# scrump.net
KiCad netlist of a schematic drawn in EAGLE
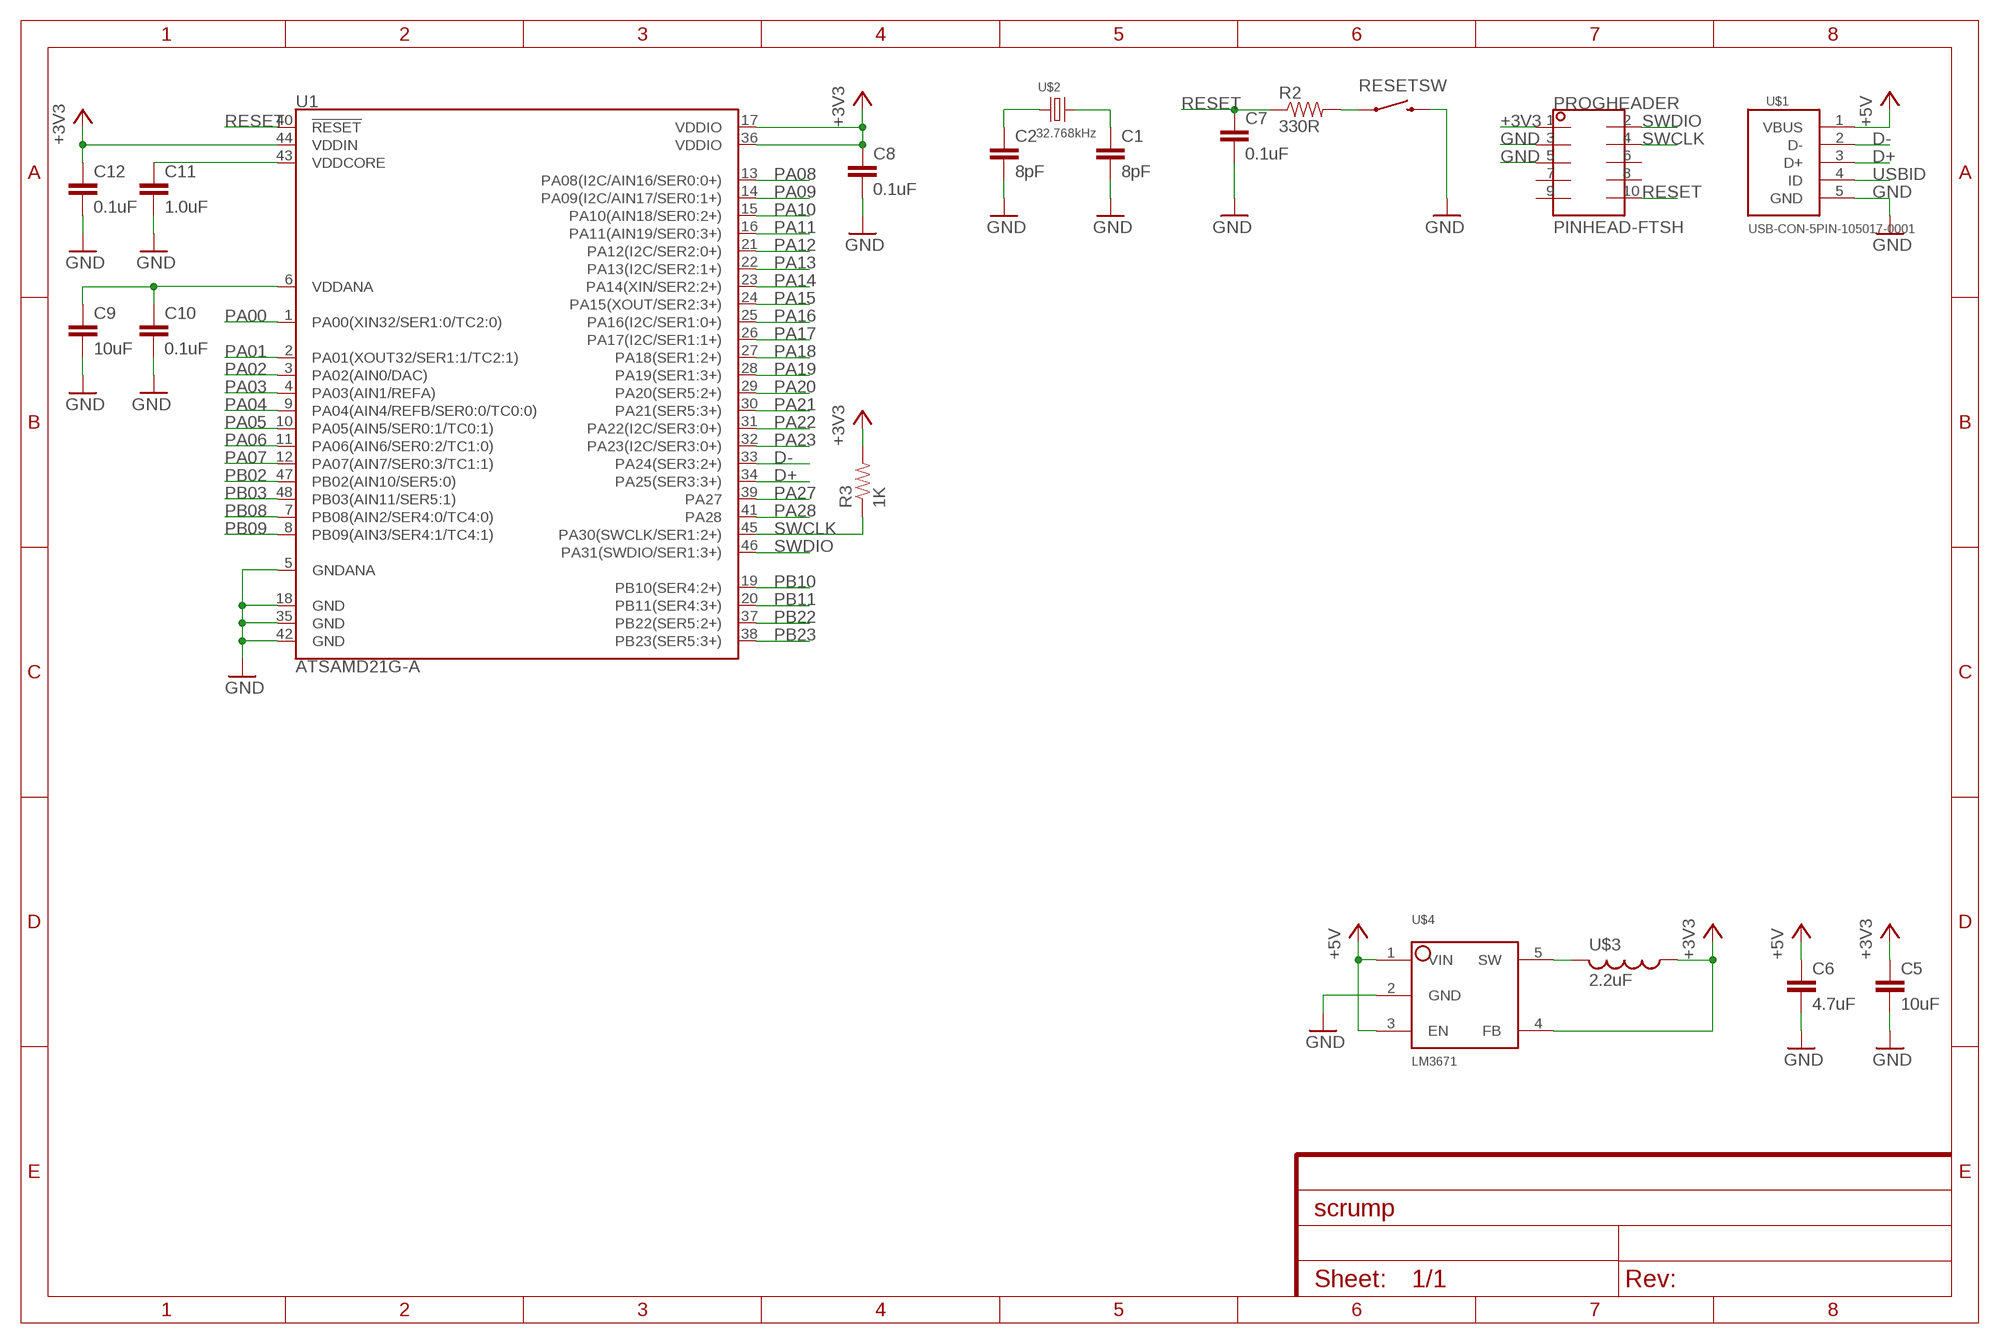
[diagram p0: schematic, sheet 1]

(export (version "E")
  (design (tool "Eeschema 10.0.6"))
  (components
    (comp (ref "C1")
      (value "8pF")
      (footprint "eagle-import:0603-CAP")
      (libsource (lib "eagle-import") (part "CAP0603-CAP"))
    )
    (comp (ref "C2")
      (value "8pF")
      (footprint "eagle-import:0603-CAP")
      (libsource (lib "eagle-import") (part "CAP0603-CAP"))
    )
    (comp (ref "C5")
      (value "10uF")
      (footprint "eagle-import:0603-CAP")
      (libsource (lib "eagle-import") (part "CAP0603-CAP"))
    )
    (comp (ref "C6")
      (value "4.7uF")
      (footprint "eagle-import:0603-CAP")
      (libsource (lib "eagle-import") (part "CAP0603-CAP"))
    )
    (comp (ref "C7")
      (value "0.1uF")
      (footprint "eagle-import:0603-CAP")
      (libsource (lib "eagle-import") (part "0.1UF-25V(+80/-20%)(0603)"))
    )
    (comp (ref "C8")
      (value "0.1uF")
      (footprint "eagle-import:0603-CAP")
      (libsource (lib "eagle-import") (part "CAP0603-CAP"))
    )
    (comp (ref "C9")
      (value "10uF")
      (footprint "eagle-import:0603-CAP")
      (libsource (lib "eagle-import") (part "CAP0603-CAP"))
    )
    (comp (ref "C10")
      (value "0.1uF")
      (footprint "eagle-import:0603-CAP")
      (libsource (lib "eagle-import") (part "CAP0603-CAP"))
    )
    (comp (ref "C11")
      (value "1.0uF")
      (footprint "eagle-import:0603-CAP")
      (libsource (lib "eagle-import") (part "CAP0603-CAP"))
    )
    (comp (ref "C12")
      (value "0.1uF")
      (footprint "eagle-import:0603-CAP")
      (libsource (lib "eagle-import") (part "CAP0603-CAP"))
    )
    (comp (ref "PROGHEADER")
      (value "PINHEAD-FTSH")
      (footprint "eagle-import:FTSH-105-01-XXX-DV-K")
      (libsource (lib "eagle-import") (part "PINHEAD-FTSH"))
    )
    (comp (ref "R2")
      (value "330R")
      (footprint "eagle-import:0603-RES")
      (libsource (lib "eagle-import") (part "RESISTOR0603"))
    )
    (comp (ref "R3")
      (value "1K")
      (footprint "eagle-import:0603-RES")
      (libsource (lib "eagle-import") (part "RESISTOR0603"))
    )
    (comp (ref "RESETSW")
      (value "PUSHBUTTON-SMD")
      (footprint "eagle-import:TACTILE-SMD-SWITCH")
      (libsource (lib "eagle-import") (part "PUSHBUTTON-SMD"))
    )
    (comp (ref "U$1")
      (value "USB-CON-5PIN-105017-0001")
      (footprint "eagle-import:USB-MICRO-MOLEX-105017-0001")
      (libsource (lib "eagle-import") (part "USB-CON-5PIN-105017-0001"))
    )
    (comp (ref "U$2")
      (value "32.768kHz")
      (footprint "eagle-import:ABS25")
      (libsource (lib "eagle-import") (part "CRYSTAL"))
    )
    (comp (ref "U$3")
      (value "2.2uF")
      (footprint "eagle-import:0806-INDUCTOR")
      (libsource (lib "eagle-import") (part "INDUCTOR"))
    )
    (comp (ref "U$4")
      (value "LM3671")
      (footprint "eagle-import:SOT23-5")
      (libsource (lib "eagle-import") (part "LM3671"))
    )
    (comp (ref "U1")
      (value "ATSAMD21G-A")
      (footprint "eagle-import:TQFP-48")
      (libsource (lib "eagle-import") (part "ATSAMD21G-A"))
    )
  )
  (nets
    (net (code "1") (name "+3V3") (class "Default")
      (node (ref "C12") (pin "1") (pinfunction "1_1") (pintype "passive"))
      (node (ref "C5") (pin "1") (pinfunction "1_1") (pintype "passive"))
      (node (ref "C8") (pin "1") (pinfunction "1_1") (pintype "passive"))
      (node (ref "PROGHEADER") (pin "1") (pinfunction "P$1_1") (pintype "bidirectional"))
      (node (ref "R3") (pin "2") (pinfunction "2_2") (pintype "passive"))
      (node (ref "U$3") (pin "1") (pinfunction "1_1") (pintype "passive"))
      (node (ref "U$4") (pin "4") (pinfunction "FB_4") (pintype "bidirectional"))
      (node (ref "U1") (pin "17") (pinfunction "VDDIO_17") (pintype "bidirectional"))
      (node (ref "U1") (pin "36") (pinfunction "VDDIO_36") (pintype "bidirectional"))
      (node (ref "U1") (pin "44") (pinfunction "VDDIN_44") (pintype "bidirectional"))
    )
    (net (code "2") (name "+5V") (class "Default")
      (node (ref "C6") (pin "1") (pinfunction "1_1") (pintype "passive"))
      (node (ref "U$1") (pin "1") (pinfunction "VBUS_1") (pintype "power_in"))
      (node (ref "U$4") (pin "1") (pinfunction "VIN_1") (pintype "bidirectional"))
      (node (ref "U$4") (pin "3") (pinfunction "EN_3") (pintype "bidirectional"))
    )
    (net (code "3") (name "/D+") (class "Default")
      (node (ref "U$1") (pin "3") (pinfunction "D+_3") (pintype "bidirectional"))
      (node (ref "U1") (pin "34") (pinfunction "PA25(SER3:3+)_34") (pintype "bidirectional"))
    )
    (net (code "4") (name "/D-") (class "Default")
      (node (ref "U$1") (pin "2") (pinfunction "D-_2") (pintype "bidirectional"))
      (node (ref "U1") (pin "33") (pinfunction "PA24(SER3:2+)_33") (pintype "bidirectional"))
    )
    (net (code "5") (name "/PA00") (class "Default")
      (node (ref "C2") (pin "1") (pinfunction "1_1") (pintype "passive"))
      (node (ref "U$2") (pin "P$1") (pinfunction "1_P$1") (pintype "passive"))
      (node (ref "U1") (pin "1") (pinfunction "PA00(XIN32/SER1:0/TC2:0)_1") (pintype "bidirectional"))
    )
    (net (code "6") (name "/PA01") (class "Default")
      (node (ref "C1") (pin "1") (pinfunction "1_1") (pintype "passive"))
      (node (ref "U$2") (pin "P$4") (pinfunction "3_P$4") (pintype "passive"))
      (node (ref "U1") (pin "2") (pinfunction "PA01(XOUT32/SER1:1/TC2:1)_2") (pintype "bidirectional"))
    )
    (net (code "7") (name "/PA02") (class "Default")
      (node (ref "U1") (pin "3") (pinfunction "PA02(AIN0/DAC)_3") (pintype "bidirectional"))
    )
    (net (code "8") (name "/PA03") (class "Default")
      (node (ref "U1") (pin "4") (pinfunction "PA03(AIN1/REFA)_4") (pintype "bidirectional"))
    )
    (net (code "9") (name "/PA04") (class "Default")
      (node (ref "U1") (pin "9") (pinfunction "PA04(AIN4/REFB/SER0:0/TC0:0)_9") (pintype "bidirectional"))
    )
    (net (code "10") (name "/PA05") (class "Default")
      (node (ref "U1") (pin "10") (pinfunction "PA05(AIN5/SER0:1/TC0:1)_10") (pintype "bidirectional"))
    )
    (net (code "11") (name "/PA06") (class "Default")
      (node (ref "U1") (pin "11") (pinfunction "PA06(AIN6/SER0:2/TC1:0)_11") (pintype "bidirectional"))
    )
    (net (code "12") (name "/PA07") (class "Default")
      (node (ref "U1") (pin "12") (pinfunction "PA07(AIN7/SER0:3/TC1:1)_12") (pintype "bidirectional"))
    )
    (net (code "13") (name "/PA08") (class "Default")
      (node (ref "U1") (pin "13") (pinfunction "PA08(I2C/AIN16/SER0:0+)_13") (pintype "bidirectional"))
    )
    (net (code "14") (name "/PA09") (class "Default")
      (node (ref "U1") (pin "14") (pinfunction "PA09(I2C/AIN17/SER0:1+)_14") (pintype "bidirectional"))
    )
    (net (code "15") (name "/PA10") (class "Default")
      (node (ref "U1") (pin "15") (pinfunction "PA10(AIN18/SER0:2+)_15") (pintype "bidirectional"))
    )
    (net (code "16") (name "/PA11") (class "Default")
      (node (ref "U1") (pin "16") (pinfunction "PA11(AIN19/SER0:3+)_16") (pintype "bidirectional"))
    )
    (net (code "17") (name "/PA12") (class "Default")
      (node (ref "U1") (pin "21") (pinfunction "PA12(I2C/SER2:0+)_21") (pintype "bidirectional"))
    )
    (net (code "18") (name "/PA13") (class "Default")
      (node (ref "U1") (pin "22") (pinfunction "PA13(I2C/SER2:1+)_22") (pintype "bidirectional"))
    )
    (net (code "19") (name "/PA14") (class "Default")
      (node (ref "U1") (pin "23") (pinfunction "PA14(XIN/SER2:2+)_23") (pintype "bidirectional"))
    )
    (net (code "20") (name "/PA15") (class "Default")
      (node (ref "U1") (pin "24") (pinfunction "PA15(XOUT/SER2:3+)_24") (pintype "bidirectional"))
    )
    (net (code "21") (name "/PA16") (class "Default")
      (node (ref "U1") (pin "25") (pinfunction "PA16(I2C/SER1:0+)_25") (pintype "bidirectional"))
    )
    (net (code "22") (name "/PA17") (class "Default")
      (node (ref "U1") (pin "26") (pinfunction "PA17(I2C/SER1:1+)_26") (pintype "bidirectional"))
    )
    (net (code "23") (name "/PA18") (class "Default")
      (node (ref "U1") (pin "27") (pinfunction "PA18(SER1:2+)_27") (pintype "bidirectional"))
    )
    (net (code "24") (name "/PA19") (class "Default")
      (node (ref "U1") (pin "28") (pinfunction "PA19(SER1:3+)_28") (pintype "bidirectional"))
    )
    (net (code "25") (name "/PA20") (class "Default")
      (node (ref "U1") (pin "29") (pinfunction "PA20(SER5:2+)_29") (pintype "bidirectional"))
    )
    (net (code "26") (name "/PA21") (class "Default")
      (node (ref "U1") (pin "30") (pinfunction "PA21(SER5:3+)_30") (pintype "bidirectional"))
    )
    (net (code "27") (name "/PA22") (class "Default")
      (node (ref "U1") (pin "31") (pinfunction "PA22(I2C/SER3:0+)_31") (pintype "bidirectional"))
    )
    (net (code "28") (name "/PA23") (class "Default")
      (node (ref "U1") (pin "32") (pinfunction "PA23(I2C/SER3:0+)_32") (pintype "bidirectional"))
    )
    (net (code "29") (name "/PA27") (class "Default")
      (node (ref "U1") (pin "39") (pinfunction "PA27_39") (pintype "bidirectional"))
    )
    (net (code "30") (name "/PA28") (class "Default")
      (node (ref "U1") (pin "41") (pinfunction "PA28_41") (pintype "bidirectional"))
    )
    (net (code "31") (name "/PB02") (class "Default")
      (node (ref "U1") (pin "47") (pinfunction "PB02(AIN10/SER5:0)_47") (pintype "bidirectional"))
    )
    (net (code "32") (name "/PB03") (class "Default")
      (node (ref "U1") (pin "48") (pinfunction "PB03(AIN11/SER5:1)_48") (pintype "bidirectional"))
    )
    (net (code "33") (name "/PB08") (class "Default")
      (node (ref "U1") (pin "7") (pinfunction "PB08(AIN2/SER4:0/TC4:0)_7") (pintype "bidirectional"))
    )
    (net (code "34") (name "/PB09") (class "Default")
      (node (ref "U1") (pin "8") (pinfunction "PB09(AIN3/SER4:1/TC4:1)_8") (pintype "bidirectional"))
    )
    (net (code "35") (name "/PB10") (class "Default")
      (node (ref "U1") (pin "19") (pinfunction "PB10(SER4:2+)_19") (pintype "bidirectional"))
    )
    (net (code "36") (name "/PB11") (class "Default")
      (node (ref "U1") (pin "20") (pinfunction "PB11(SER4:3+)_20") (pintype "bidirectional"))
    )
    (net (code "37") (name "/PB22") (class "Default")
      (node (ref "U1") (pin "37") (pinfunction "PB22(SER5:2+)_37") (pintype "bidirectional"))
    )
    (net (code "38") (name "/PB23") (class "Default")
      (node (ref "U1") (pin "38") (pinfunction "PB23(SER5:3+)_38") (pintype "bidirectional"))
    )
    (net (code "39") (name "/RESET") (class "Default")
      (node (ref "C7") (pin "1") (pinfunction "1_1") (pintype "passive"))
      (node (ref "PROGHEADER") (pin "10") (pinfunction "P$10_10") (pintype "bidirectional"))
      (node (ref "R2") (pin "1") (pinfunction "1_1") (pintype "passive"))
      (node (ref "U1") (pin "40") (pinfunction "~{RESET}_40") (pintype "bidirectional"))
    )
    (net (code "40") (name "/SWCLK") (class "Default")
      (node (ref "PROGHEADER") (pin "4") (pinfunction "P$4_4") (pintype "bidirectional"))
      (node (ref "R3") (pin "1") (pinfunction "1_1") (pintype "passive"))
      (node (ref "U1") (pin "45") (pinfunction "PA30(SWCLK/SER1:2+)_45") (pintype "bidirectional"))
    )
    (net (code "41") (name "/SWDIO") (class "Default")
      (node (ref "PROGHEADER") (pin "2") (pinfunction "P$2_2") (pintype "bidirectional"))
      (node (ref "U1") (pin "46") (pinfunction "PA31(SWDIO/SER1:3+)_46") (pintype "bidirectional"))
    )
    (net (code "42") (name "/USBID") (class "Default")
      (node (ref "U$1") (pin "4") (pinfunction "ID_4") (pintype "bidirectional"))
    )
    (net (code "43") (name "GND") (class "Default")
      (node (ref "C1") (pin "2") (pinfunction "2_2") (pintype "passive"))
      (node (ref "C10") (pin "2") (pinfunction "2_2") (pintype "passive"))
      (node (ref "C11") (pin "2") (pinfunction "2_2") (pintype "passive"))
      (node (ref "C12") (pin "2") (pinfunction "2_2") (pintype "passive"))
      (node (ref "C2") (pin "2") (pinfunction "2_2") (pintype "passive"))
      (node (ref "C5") (pin "2") (pinfunction "2_2") (pintype "passive"))
      (node (ref "C6") (pin "2") (pinfunction "2_2") (pintype "passive"))
      (node (ref "C7") (pin "2") (pinfunction "2_2") (pintype "passive"))
      (node (ref "C8") (pin "2") (pinfunction "2_2") (pintype "passive"))
      (node (ref "C9") (pin "2") (pinfunction "2_2") (pintype "passive"))
      (node (ref "PROGHEADER") (pin "3") (pinfunction "P$3_3") (pintype "bidirectional"))
      (node (ref "PROGHEADER") (pin "5") (pinfunction "P$5_5") (pintype "bidirectional"))
      (node (ref "RESETSW") (pin "P$3") (pinfunction "2_P$3") (pintype "passive"))
      (node (ref "RESETSW") (pin "P$4") (pinfunction "2_P$4") (pintype "passive"))
      (node (ref "U$1") (pin "5") (pinfunction "GND_5") (pintype "power_in"))
      (node (ref "U$4") (pin "2") (pinfunction "GND_2") (pintype "bidirectional"))
      (node (ref "U1") (pin "18") (pinfunction "GND_18") (pintype "bidirectional"))
      (node (ref "U1") (pin "35") (pinfunction "GND_35") (pintype "bidirectional"))
      (node (ref "U1") (pin "42") (pinfunction "GND_42") (pintype "bidirectional"))
      (node (ref "U1") (pin "5") (pinfunction "GNDANA_5") (pintype "bidirectional"))
    )
    (net (code "44") (name "Net-(R2-Pad2)") (class "Default")
      (node (ref "R2") (pin "2") (pinfunction "2_2") (pintype "passive"))
      (node (ref "RESETSW") (pin "P$1") (pinfunction "1_P$1") (pintype "passive"))
      (node (ref "RESETSW") (pin "P$2") (pinfunction "1_P$2") (pintype "passive"))
    )
    (net (code "45") (name "Net-(U$4-SW)") (class "Default")
      (node (ref "U$3") (pin "2") (pinfunction "2_2") (pintype "passive"))
      (node (ref "U$4") (pin "5") (pinfunction "SW_5") (pintype "bidirectional"))
    )
    (net (code "46") (name "Net-(U1-VDDANA)") (class "Default")
      (node (ref "C10") (pin "1") (pinfunction "1_1") (pintype "passive"))
      (node (ref "C9") (pin "1") (pinfunction "1_1") (pintype "passive"))
      (node (ref "U1") (pin "6") (pinfunction "VDDANA_6") (pintype "bidirectional"))
    )
    (net (code "47") (name "Net-(U1-VDDCORE)") (class "Default")
      (node (ref "C11") (pin "1") (pinfunction "1_1") (pintype "passive"))
      (node (ref "U1") (pin "43") (pinfunction "VDDCORE_43") (pintype "bidirectional"))
    )
    (net (code "48") (name "unconnected-(PROGHEADER-P$6-Pad6)") (class "Default")
      (node (ref "PROGHEADER") (pin "6") (pinfunction "P$6_6") (pintype "bidirectional"))
    )
    (net (code "49") (name "unconnected-(PROGHEADER-P$7-Pad7)") (class "Default")
      (node (ref "PROGHEADER") (pin "7") (pinfunction "P$7_7") (pintype "bidirectional"))
    )
    (net (code "50") (name "unconnected-(PROGHEADER-P$8-Pad8)") (class "Default")
      (node (ref "PROGHEADER") (pin "8") (pinfunction "P$8_8") (pintype "bidirectional"))
    )
    (net (code "51") (name "unconnected-(PROGHEADER-P$9-Pad9)") (class "Default")
      (node (ref "PROGHEADER") (pin "9") (pinfunction "P$9_9") (pintype "bidirectional"))
    )
  )
)
